# main.net
KiCad netlist of a schematic drawn in Altium Designer
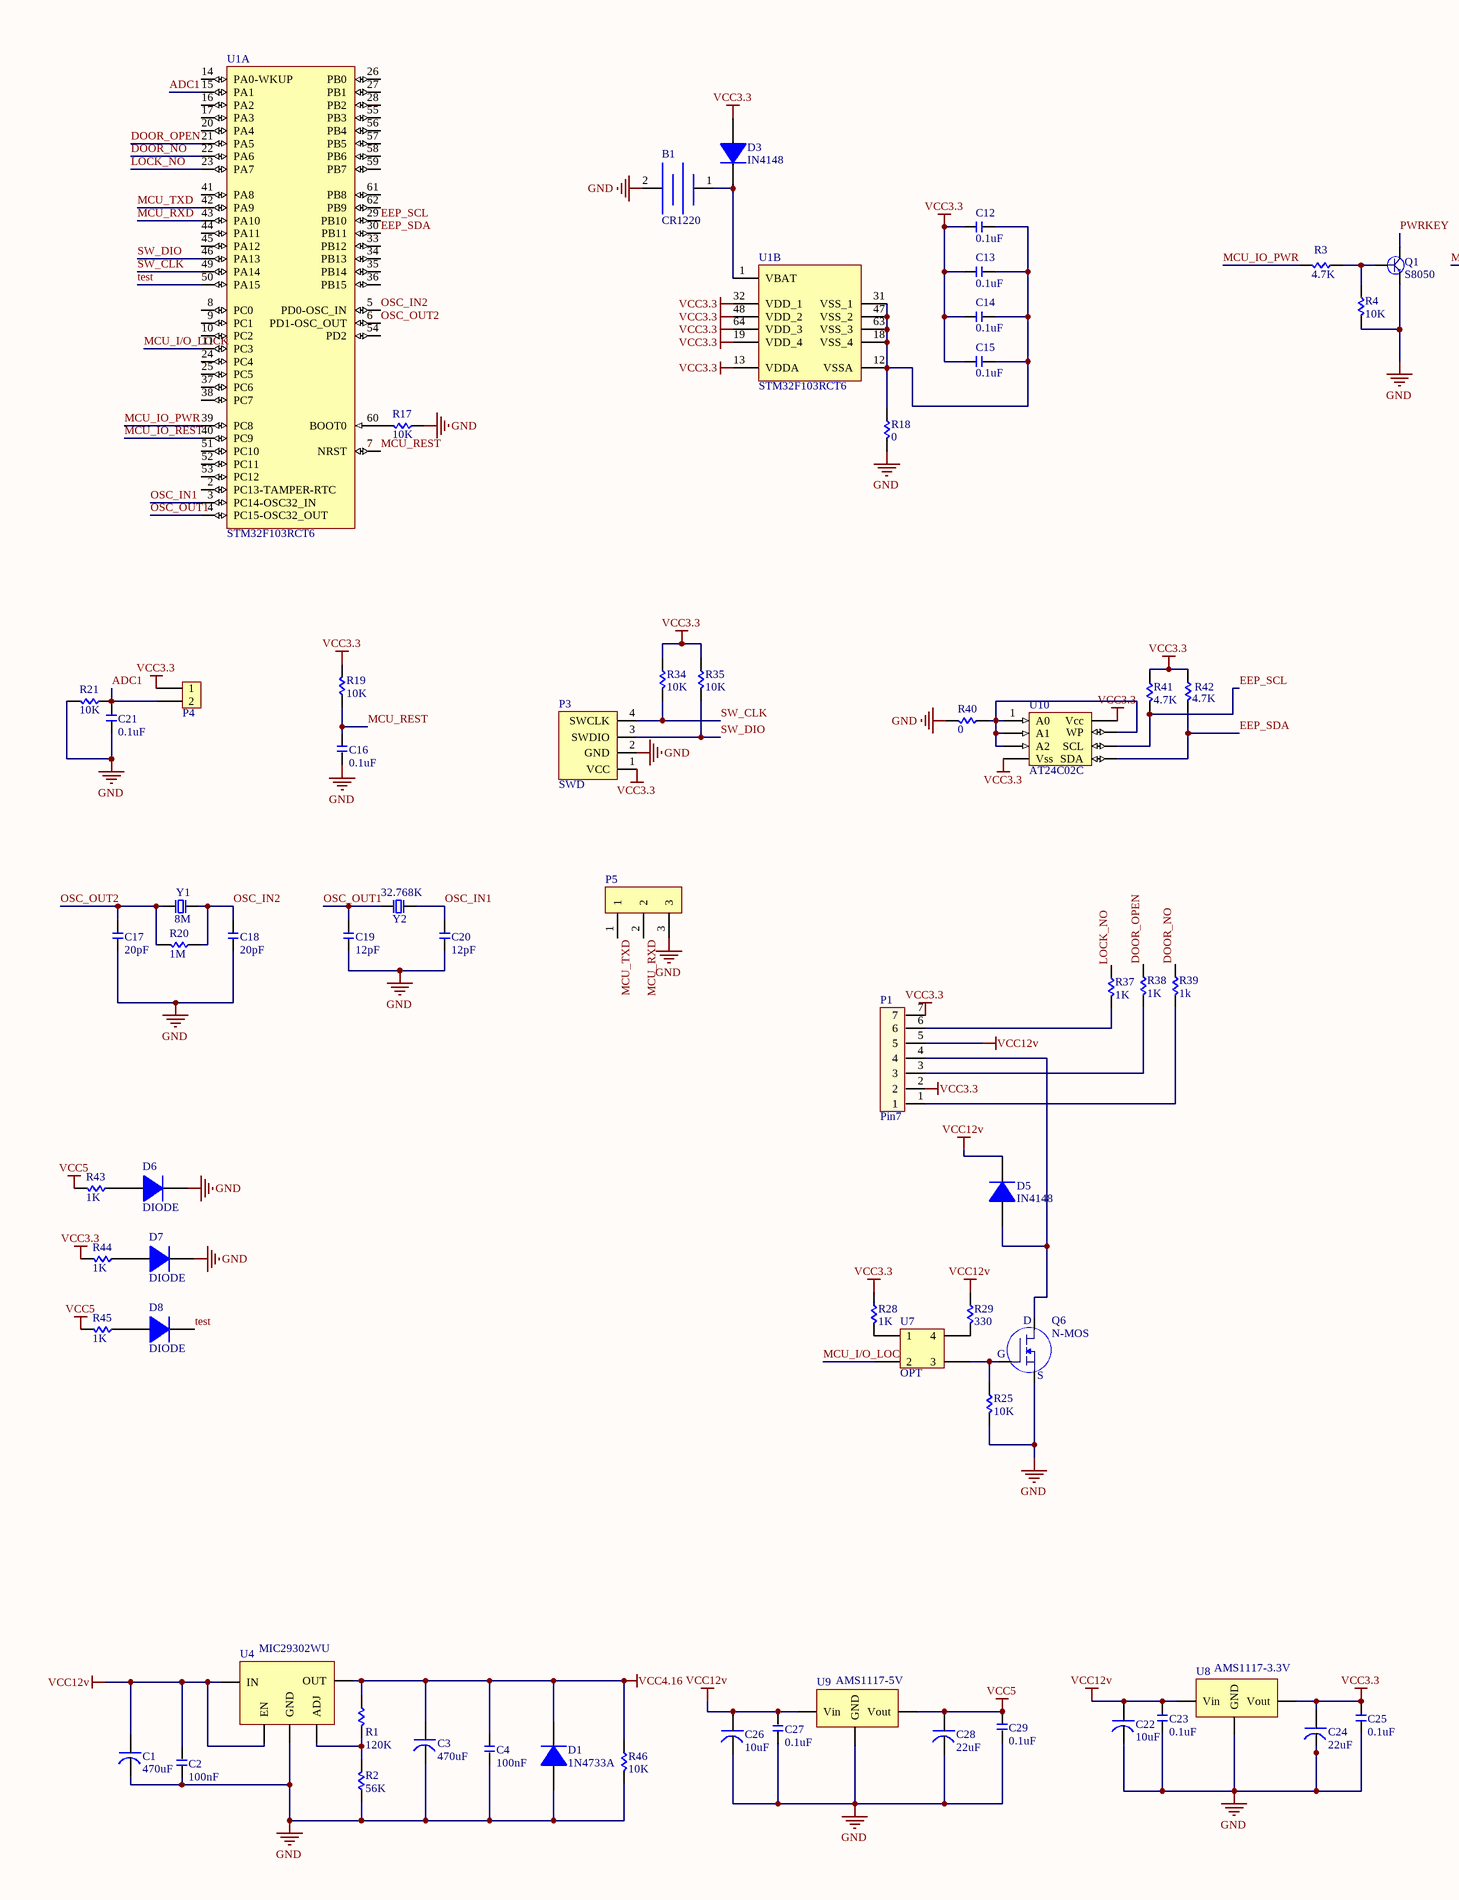
[diagram p0: main.SchDoc, left]
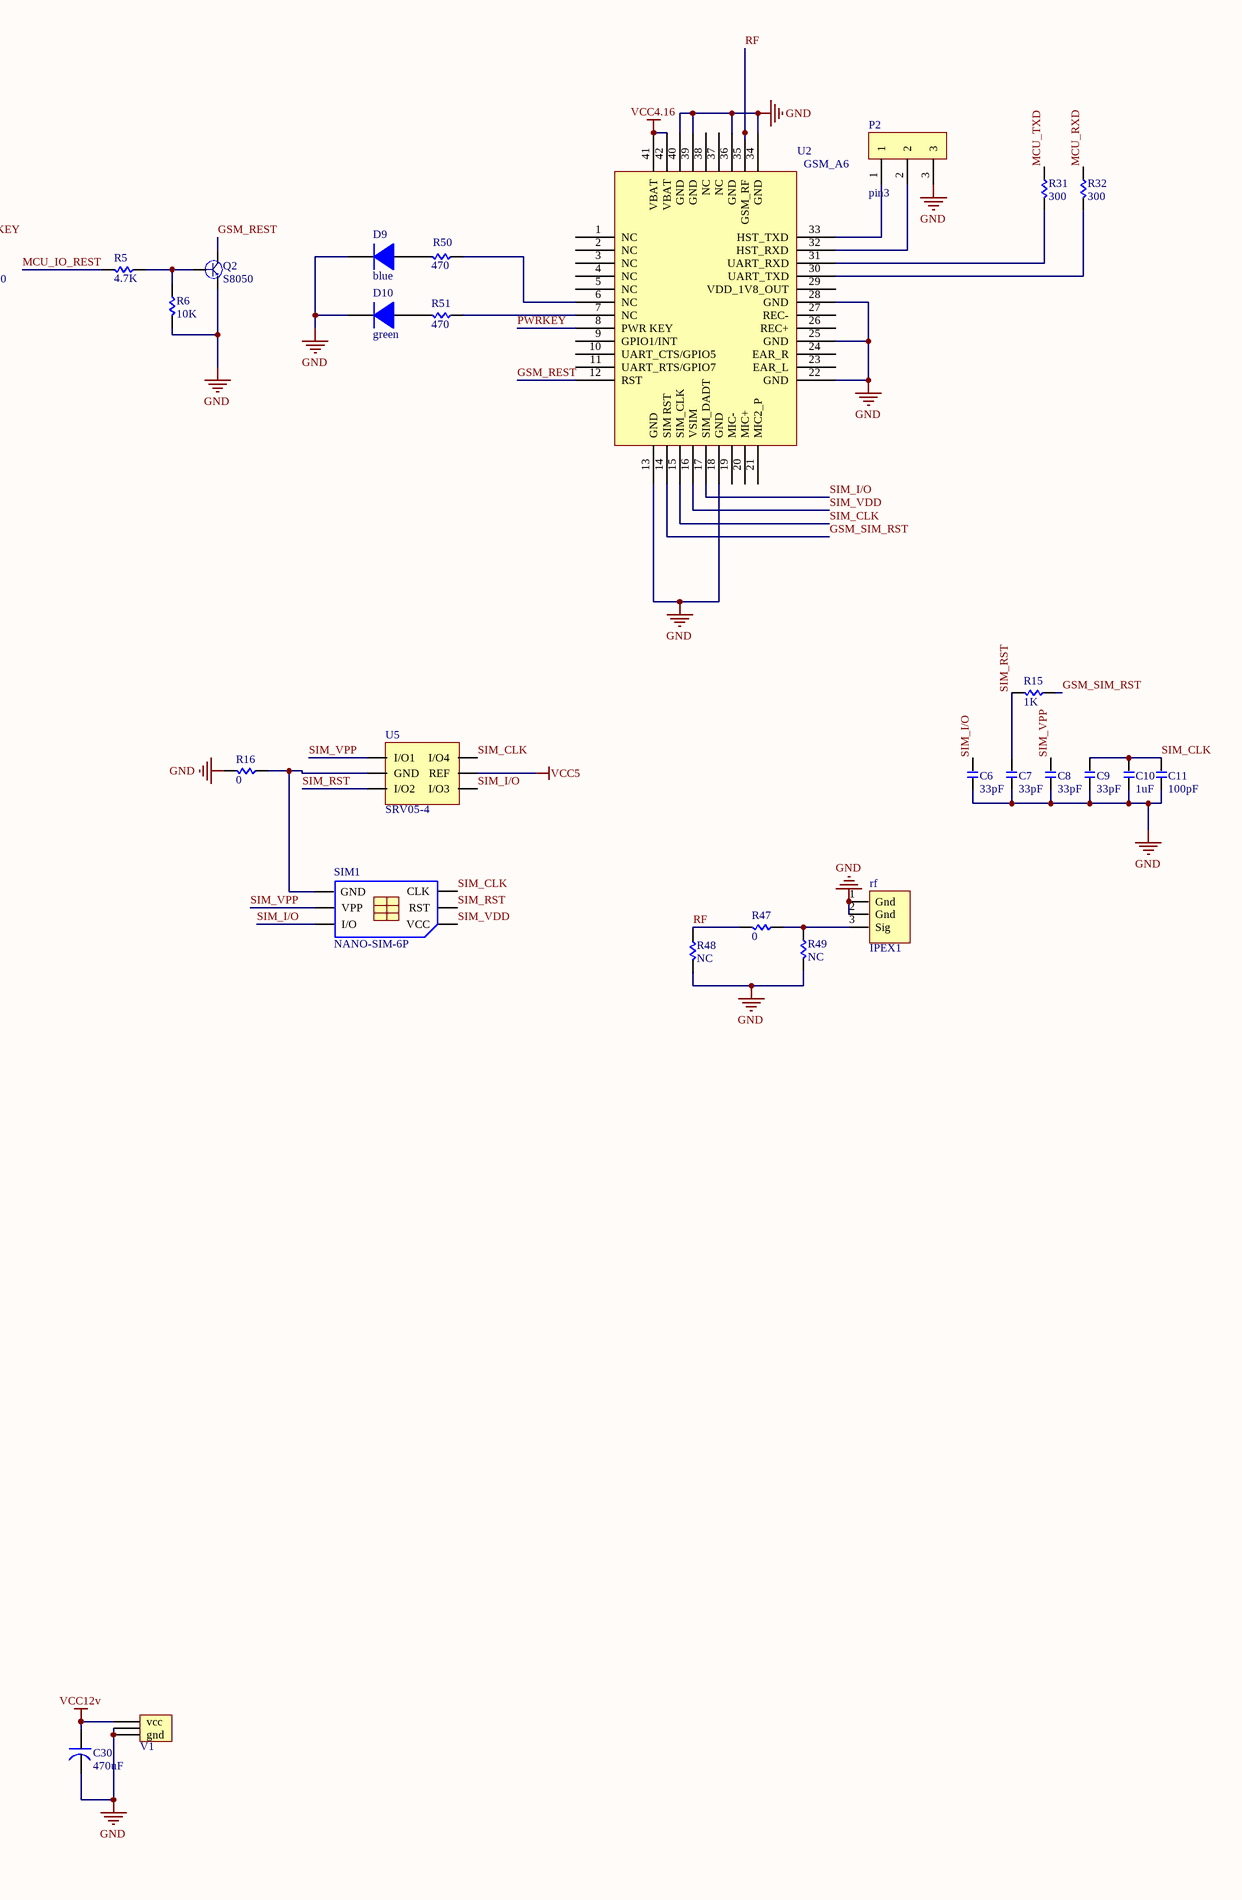
[diagram p1: main.SchDoc, right]

(export (version "E")
  (design (tool "Eeschema 10.0.6"))
  (components
    (comp (ref "B1") (value "CR1220") (footprint "CR1220") (libsource (lib "dev") (part "BAT")))
    (comp (ref "C1") (value "470uF") (footprint "CAP_8.2mm*8.2mm") (libsource (lib "dev") (part "Cap_Elec")))
    (comp (ref "C2") (value "100nF") (footprint "0805") (libsource (lib "dev") (part "Cap")))
    (comp (ref "C3") (value "470uF") (footprint "CAP_8.2mm*8.2mm") (libsource (lib "dev") (part "Cap_Elec")))
    (comp (ref "C4") (value "100nF") (footprint "0805") (libsource (lib "dev") (part "Cap")))
    (comp (ref "C6") (value "33pF") (footprint "0805") (libsource (lib "dev") (part "Cap")))
    (comp (ref "C7") (value "33pF") (footprint "0805") (libsource (lib "dev") (part "Cap")))
    (comp (ref "C8") (value "33pF") (footprint "0805") (libsource (lib "dev") (part "Cap")))
    (comp (ref "C9") (value "33pF") (footprint "0805") (libsource (lib "dev") (part "Cap")))
    (comp (ref "C10") (value "1uF") (footprint "0805") (libsource (lib "dev") (part "Cap")))
    (comp (ref "C11") (value "100pF") (footprint "0805") (libsource (lib "dev") (part "Cap")))
    (comp (ref "C12") (value "0.1uF") (footprint "0805") (libsource (lib "dev") (part "Cap")))
    (comp (ref "C13") (value "0.1uF") (footprint "0805") (libsource (lib "dev") (part "Cap")))
    (comp (ref "C14") (value "0.1uF") (footprint "0805") (libsource (lib "dev") (part "Cap")))
    (comp (ref "C15") (value "0.1uF") (footprint "0805") (libsource (lib "dev") (part "Cap")))
    (comp (ref "C16") (value "0.1uF") (footprint "0805") (libsource (lib "dev") (part "Cap")))
    (comp (ref "C17") (value "20pF") (footprint "0805") (libsource (lib "dev") (part "Cap")))
    (comp (ref "C18") (value "20pF") (footprint "0805") (libsource (lib "dev") (part "Cap")))
    (comp (ref "C19") (value "12pF") (footprint "0805") (libsource (lib "dev") (part "Cap")))
    (comp (ref "C20") (value "12pF") (footprint "0805") (libsource (lib "dev") (part "Cap")))
    (comp (ref "C21") (value "0.1uF") (footprint "0805") (libsource (lib "dev") (part "Cap")))
    (comp (ref "C22") (value "10uF") (footprint "1206") (libsource (lib "dev") (part "Cap_Elec")))
    (comp (ref "C23") (value "0.1uF") (footprint "0805") (libsource (lib "dev") (part "Cap")))
    (comp (ref "C24") (value "22uF") (footprint "1206") (libsource (lib "dev") (part "Cap_Elec")))
    (comp (ref "C25") (value "0.1uF") (footprint "0805") (libsource (lib "dev") (part "Cap")))
    (comp (ref "C26") (value "10uF") (footprint "1206") (libsource (lib "dev") (part "Cap_Elec")))
    (comp (ref "C27") (value "0.1uF") (footprint "0805") (libsource (lib "dev") (part "Cap")))
    (comp (ref "C28") (value "22uF") (footprint "1206") (libsource (lib "dev") (part "Cap_Elec")))
    (comp (ref "C29") (value "0.1uF") (footprint "0805") (libsource (lib "dev") (part "Cap")))
    (comp (ref "C30") (value "470uF") (footprint "DIP2_8.3x3.1") (libsource (lib "dev") (part "Cap_Elec")))
    (comp (ref "D1") (value "1N4733A") (footprint "Dip-6mm") (libsource (lib "dev") (part "DIODE")))
    (comp (ref "D3") (value "IN4148") (footprint "1206") (libsource (lib "dev") (part "DIODE")))
    (comp (ref "D5") (value "IN4148") (footprint "1206") (libsource (lib "dev") (part "DIODE")))
    (comp (ref "D6") (value "DIODE") (footprint "0603") (libsource (lib "dev") (part "DIODE")))
    (comp (ref "D7") (value "DIODE") (footprint "0603") (libsource (lib "dev") (part "DIODE")))
    (comp (ref "D8") (value "DIODE") (footprint "0603") (libsource (lib "dev") (part "DIODE")))
    (comp (ref "D9") (value "blue") (footprint "0603") (libsource (lib "dev") (part "DIODE")))
    (comp (ref "D10") (value "green") (footprint "0603") (libsource (lib "dev") (part "DIODE")))
    (comp (ref "P1") (value "Pin7") (footprint "Pin_7_3.5mm") (libsource (lib "dev") (part "Pin7")))
    (comp (ref "P2") (value "pin3") (footprint "PIN3") (libsource (lib "dev") (part "pin3")))
    (comp (ref "P3") (value "SWD") (footprint "PIN4") (libsource (lib "dev") (part "SWD")))
    (comp (ref "P4") (value "Pin2") (footprint "XH2.54_2") (libsource (lib "dev") (part "Pin2")))
    (comp (ref "P5") (value "pin3") (footprint "PIN3") (libsource (lib "dev") (part "pin3")))
    (comp (ref "Q1") (value "S8050") (footprint "sot-23") (libsource (lib "dev") (part "Npn-Sot-23")))
    (comp (ref "Q2") (value "S8050") (footprint "sot-23") (libsource (lib "dev") (part "Npn-Sot-23")))
    (comp (ref "Q6") (value "N-MOS") (footprint "SOT-23-3") (libsource (lib "dev") (part "N-MOS")))
    (comp (ref "R1") (value "120K") (footprint "0805") (libsource (lib "dev") (part "Res")))
    (comp (ref "R2") (value "56K") (footprint "0805") (libsource (lib "dev") (part "Res")))
    (comp (ref "R3") (value "4.7K") (footprint "0805") (libsource (lib "dev") (part "Res")))
    (comp (ref "R4") (value "10K") (footprint "0805") (libsource (lib "dev") (part "Res")))
    (comp (ref "R5") (value "4.7K") (footprint "0805") (libsource (lib "dev") (part "Res")))
    (comp (ref "R6") (value "10K") (footprint "0805") (libsource (lib "dev") (part "Res")))
    (comp (ref "R15") (value "1K") (footprint "0805") (libsource (lib "dev") (part "Res")))
    (comp (ref "R16") (value "0") (footprint "0603") (libsource (lib "dev") (part "Res")))
    (comp (ref "R17") (value "10K") (footprint "0805") (libsource (lib "dev") (part "Res")))
    (comp (ref "R18") (value "0") (footprint "0603") (libsource (lib "dev") (part "Res")))
    (comp (ref "R19") (value "10K") (footprint "0805") (libsource (lib "dev") (part "Res")))
    (comp (ref "R20") (value "1M") (footprint "0805") (libsource (lib "dev") (part "Res")))
    (comp (ref "R21") (value "10K") (footprint "0805") (libsource (lib "dev") (part "Res")))
    (comp (ref "R25") (value "10K") (footprint "0805") (libsource (lib "dev") (part "Res")))
    (comp (ref "R28") (value "1K") (footprint "0805") (libsource (lib "dev") (part "Res")))
    (comp (ref "R29") (value "330") (footprint "0805") (libsource (lib "dev") (part "Res")))
    (comp (ref "R31") (value "300") (footprint "0805") (libsource (lib "dev") (part "Res")))
    (comp (ref "R32") (value "300") (footprint "0805") (libsource (lib "dev") (part "Res")))
    (comp (ref "R34") (value "10K") (footprint "0805") (libsource (lib "dev") (part "Res")))
    (comp (ref "R35") (value "10K") (footprint "0805") (libsource (lib "dev") (part "Res")))
    (comp (ref "R37") (value "1K") (footprint "0805") (libsource (lib "dev") (part "Res")))
    (comp (ref "R38") (value "1K") (footprint "0805") (libsource (lib "dev") (part "Res")))
    (comp (ref "R39") (value "1k") (footprint "0805") (libsource (lib "dev") (part "Res")))
    (comp (ref "R40") (value "0") (footprint "0603") (libsource (lib "dev") (part "Res")))
    (comp (ref "R41") (value "4.7K") (footprint "0603") (libsource (lib "dev") (part "Res")))
    (comp (ref "R42") (value "4.7K") (footprint "0603") (libsource (lib "dev") (part "Res")))
    (comp (ref "R43") (value "1K") (footprint "0603") (libsource (lib "dev") (part "Res")))
    (comp (ref "R44") (value "1K") (footprint "0603") (libsource (lib "dev") (part "Res")))
    (comp (ref "R45") (value "1K") (footprint "0603") (libsource (lib "dev") (part "Res")))
    (comp (ref "R46") (value "10K") (footprint "0805") (libsource (lib "dev") (part "Res")))
    (comp (ref "R47") (value "0") (footprint "0805") (libsource (lib "dev") (part "Res")))
    (comp (ref "R48") (value "NC") (footprint "0805") (libsource (lib "dev") (part "Res")))
    (comp (ref "R49") (value "NC") (footprint "0805") (libsource (lib "dev") (part "Res")))
    (comp (ref "R50") (value "470") (footprint "0603") (libsource (lib "dev") (part "Res")))
    (comp (ref "R51") (value "470") (footprint "0603") (libsource (lib "dev") (part "Res")))
    (comp (ref "rf") (value "IPEX1") (footprint "IPEX_1") (libsource (lib "dev") (part "IPEX1")))
    (comp (ref "SIM1")
      (value "NANO-SIM-6P")
      (footprint "NANO-SIM-6P")
      (libsource (lib "dev") (part "NANO-SIM-6P"))
    )
    (comp (ref "U1")
      (value "STM32F103RCT6")
      (footprint "STM-LQFP64_M")
      (libsource (lib "STMicroelectronics STM32 F1") (part "STM32F103RCT6"))
    )
    (comp (ref "U2") (value "GSM_A6") (footprint "PCBA6") (libsource (lib "Schlib1") (part "GSM_A6")))
    (comp (ref "U4") (value "MIC29302WU") (footprint "TO-263-5") (libsource (lib "dev") (part "MIC29302WU")))
    (comp (ref "U5") (value "SRV05-4") (footprint "Sot-23-6") (libsource (lib "dev") (part "SRV05-4")))
    (comp (ref "U7") (value "OPT") (footprint "SOP4") (libsource (lib "dev") (part "OPT")))
    (comp (ref "U8")
      (value "AMS1117-3.3V")
      (footprint "SOT-223")
      (libsource (lib "dev") (part "AMS1117-3.3V"))
    )
    (comp (ref "U9") (value "AMS1117-5V") (footprint "SOT-223") (libsource (lib "dev") (part "AMS1117-3.3V")))
    (comp (ref "U10") (value "AT24C02C") (footprint "SOP8") (libsource (lib "dev") (part "AT24C02C")))
    (comp (ref "V1")
      (value "POWER_PIN")
      (footprint "POWER_PIN_PCB")
      (libsource (lib "dev") (part "POWER_PIN"))
    )
    (comp (ref "Y1") (value "8M") (footprint "crystal") (libsource (lib "dev") (part "crystal")))
    (comp (ref "Y2") (value "32.768K") (footprint "PIN1.1") (libsource (lib "dev") (part "crystal")))
  )
  (nets
    (net (code "1") (name "/ADC1") (class "Default")
      (node (ref "C21") (pin "2") (pinfunction "2_2") (pintype "passive"))
      (node (ref "P4") (pin "2") (pinfunction "2_2") (pintype "passive"))
      (node (ref "R21") (pin "2") (pinfunction "2_2") (pintype "passive"))
      (node (ref "U1") (pin "15") (pinfunction "PA1_15") (pintype "bidirectional"))
    )
    (net (code "2") (name "/DOOR_NO") (class "Default")
      (node (ref "R39") (pin "2") (pinfunction "2_2") (pintype "passive"))
      (node (ref "U1") (pin "22") (pinfunction "PA6_22") (pintype "bidirectional"))
    )
    (net (code "3") (name "/DOOR_OPEN") (class "Default")
      (node (ref "R38") (pin "2") (pinfunction "2_2") (pintype "passive"))
      (node (ref "U1") (pin "21") (pinfunction "PA5_21") (pintype "bidirectional"))
    )
    (net (code "4") (name "/EEP_SCL") (class "Default")
      (node (ref "R41") (pin "1") (pinfunction "1_1") (pintype "passive"))
      (node (ref "U1") (pin "29") (pinfunction "PB10_29") (pintype "bidirectional"))
      (node (ref "U10") (pin "6") (pinfunction "SCL_6") (pintype "bidirectional"))
    )
    (net (code "5") (name "/EEP_SDA") (class "Default")
      (node (ref "R42") (pin "1") (pinfunction "1_1") (pintype "passive"))
      (node (ref "U1") (pin "30") (pinfunction "PB11_30") (pintype "bidirectional"))
      (node (ref "U10") (pin "5") (pinfunction "SDA_5") (pintype "bidirectional"))
    )
    (net (code "6") (name "/GSM_REST") (class "Default")
      (node (ref "Q2") (pin "3") (pinfunction "3_3") (pintype "passive"))
      (node (ref "U2") (pin "12") (pinfunction "RST_12") (pintype "passive"))
    )
    (net (code "7") (name "/GSM_SIM_RST") (class "Default")
      (node (ref "R15") (pin "2") (pinfunction "2_2") (pintype "passive"))
      (node (ref "U2") (pin "14") (pinfunction "SIM_RST_14") (pintype "passive"))
    )
    (net (code "8") (name "/LOCK_NO") (class "Default")
      (node (ref "R37") (pin "2") (pinfunction "2_2") (pintype "passive"))
      (node (ref "U1") (pin "23") (pinfunction "PA7_23") (pintype "bidirectional"))
    )
    (net (code "9") (name "/MCU_IO_PWR") (class "Default")
      (node (ref "R3") (pin "1") (pinfunction "1_1") (pintype "passive"))
      (node (ref "U1") (pin "39") (pinfunction "PC8_39") (pintype "bidirectional"))
    )
    (net (code "10") (name "/MCU_IO_REST") (class "Default")
      (node (ref "R5") (pin "1") (pinfunction "1_1") (pintype "passive"))
      (node (ref "U1") (pin "40") (pinfunction "PC9_40") (pintype "bidirectional"))
    )
    (net (code "11") (name "/MCU_I{slash}O_LOCK") (class "Default")
      (node (ref "U1") (pin "11") (pinfunction "PC3_11") (pintype "bidirectional"))
      (node (ref "U7") (pin "2") (pinfunction "2_2") (pintype "passive"))
    )
    (net (code "12") (name "/MCU_REST") (class "Default")
      (node (ref "C16") (pin "1") (pinfunction "1_1") (pintype "passive"))
      (node (ref "R19") (pin "2") (pinfunction "2_2") (pintype "passive"))
      (node (ref "U1") (pin "7") (pinfunction "NRST_7") (pintype "bidirectional"))
    )
    (net (code "13") (name "/MCU_RXD") (class "Default")
      (node (ref "P5") (pin "2") (pinfunction "2_2") (pintype "passive"))
      (node (ref "R32") (pin "2") (pinfunction "2_2") (pintype "passive"))
      (node (ref "U1") (pin "43") (pinfunction "PA10_43") (pintype "bidirectional"))
    )
    (net (code "14") (name "/MCU_TXD") (class "Default")
      (node (ref "P5") (pin "1") (pinfunction "1_1") (pintype "passive"))
      (node (ref "R31") (pin "2") (pinfunction "2_2") (pintype "passive"))
      (node (ref "U1") (pin "42") (pinfunction "PA9_42") (pintype "bidirectional"))
    )
    (net (code "15") (name "/OSC_IN1") (class "Default")
      (node (ref "C20") (pin "2") (pinfunction "2_2") (pintype "passive"))
      (node (ref "U1") (pin "3") (pinfunction "PC14-OSC32_IN_3") (pintype "bidirectional"))
      (node (ref "Y2") (pin "2") (pinfunction "2_2") (pintype "passive"))
    )
    (net (code "16") (name "/OSC_IN2") (class "Default")
      (node (ref "C18") (pin "2") (pinfunction "2_2") (pintype "passive"))
      (node (ref "R20") (pin "2") (pinfunction "2_2") (pintype "passive"))
      (node (ref "U1") (pin "5") (pinfunction "PD0-OSC_IN_5") (pintype "bidirectional"))
      (node (ref "Y1") (pin "2") (pinfunction "2_2") (pintype "passive"))
    )
    (net (code "17") (name "/OSC_OUT1") (class "Default")
      (node (ref "C19") (pin "2") (pinfunction "2_2") (pintype "passive"))
      (node (ref "U1") (pin "4") (pinfunction "PC15-OSC32_OUT_4") (pintype "bidirectional"))
      (node (ref "Y2") (pin "1") (pinfunction "1_1") (pintype "passive"))
    )
    (net (code "18") (name "/OSC_OUT2") (class "Default")
      (node (ref "C17") (pin "2") (pinfunction "2_2") (pintype "passive"))
      (node (ref "R20") (pin "1") (pinfunction "1_1") (pintype "passive"))
      (node (ref "U1") (pin "6") (pinfunction "PD1-OSC_OUT_6") (pintype "bidirectional"))
      (node (ref "Y1") (pin "1") (pinfunction "1_1") (pintype "passive"))
    )
    (net (code "19") (name "/PWRKEY") (class "Default")
      (node (ref "Q1") (pin "3") (pinfunction "3_3") (pintype "passive"))
      (node (ref "U2") (pin "8") (pinfunction "PWR_KEY_8") (pintype "passive"))
    )
    (net (code "20") (name "/RF") (class "Default")
      (node (ref "R47") (pin "1") (pinfunction "1_1") (pintype "passive"))
      (node (ref "R48") (pin "2") (pinfunction "2_2") (pintype "passive"))
      (node (ref "U2") (pin "35") (pinfunction "GSM_RF_35") (pintype "passive"))
    )
    (net (code "21") (name "/SIM_CLK") (class "Default")
      (node (ref "C10") (pin "2") (pinfunction "2_2") (pintype "passive"))
      (node (ref "C11") (pin "2") (pinfunction "2_2") (pintype "passive"))
      (node (ref "C9") (pin "2") (pinfunction "2_2") (pintype "passive"))
      (node (ref "SIM1") (pin "3") (pinfunction "CLK_3") (pintype "passive"))
      (node (ref "U2") (pin "15") (pinfunction "SIM_CLK_15") (pintype "passive"))
      (node (ref "U5") (pin "6") (pinfunction "I/O4_6") (pintype "passive"))
    )
    (net (code "22") (name "/SIM_I{slash}O") (class "Default")
      (node (ref "C6") (pin "2") (pinfunction "2_2") (pintype "passive"))
      (node (ref "SIM1") (pin "7") (pinfunction "I/O_7") (pintype "passive"))
      (node (ref "U2") (pin "17") (pinfunction "SIM_DADT_17") (pintype "passive"))
      (node (ref "U5") (pin "4") (pinfunction "I/O3_4") (pintype "passive"))
    )
    (net (code "23") (name "/SIM_RST") (class "Default")
      (node (ref "C7") (pin "2") (pinfunction "2_2") (pintype "passive"))
      (node (ref "R15") (pin "1") (pinfunction "1_1") (pintype "passive"))
      (node (ref "SIM1") (pin "2") (pinfunction "RST_2") (pintype "passive"))
      (node (ref "U5") (pin "3") (pinfunction "I/O2_3") (pintype "passive"))
    )
    (net (code "24") (name "/SIM_VDD") (class "Default")
      (node (ref "SIM1") (pin "1") (pinfunction "VCC_1") (pintype "passive"))
      (node (ref "U2") (pin "16") (pinfunction "VSIM_16") (pintype "passive"))
    )
    (net (code "25") (name "/SIM_VPP") (class "Default")
      (node (ref "C8") (pin "2") (pinfunction "2_2") (pintype "passive"))
      (node (ref "SIM1") (pin "6") (pinfunction "VPP_6") (pintype "passive"))
      (node (ref "U5") (pin "1") (pinfunction "I/O1_1") (pintype "passive"))
    )
    (net (code "26") (name "/SW_CLK") (class "Default")
      (node (ref "P3") (pin "4") (pinfunction "SWCLK_4") (pintype "passive"))
      (node (ref "R34") (pin "1") (pinfunction "1_1") (pintype "passive"))
      (node (ref "U1") (pin "49") (pinfunction "PA14_49") (pintype "bidirectional"))
    )
    (net (code "27") (name "/SW_DIO") (class "Default")
      (node (ref "P3") (pin "3") (pinfunction "SWDIO_3") (pintype "passive"))
      (node (ref "R35") (pin "1") (pinfunction "1_1") (pintype "passive"))
      (node (ref "U1") (pin "46") (pinfunction "PA13_46") (pintype "bidirectional"))
    )
    (net (code "28") (name "/test") (class "Default")
      (node (ref "D8") (pin "2") (pinfunction "2_2") (pintype "passive"))
      (node (ref "U1") (pin "50") (pinfunction "PA15_50") (pintype "bidirectional"))
    )
    (net (code "29") (name "GND") (class "Default")
      (node (ref "B1") (pin "2") (pinfunction "2_2") (pintype "passive"))
      (node (ref "C1") (pin "2") (pinfunction "2_2") (pintype "passive"))
      (node (ref "C10") (pin "1") (pinfunction "1_1") (pintype "passive"))
      (node (ref "C11") (pin "1") (pinfunction "1_1") (pintype "passive"))
      (node (ref "C16") (pin "2") (pinfunction "2_2") (pintype "passive"))
      (node (ref "C17") (pin "1") (pinfunction "1_1") (pintype "passive"))
      (node (ref "C18") (pin "1") (pinfunction "1_1") (pintype "passive"))
      (node (ref "C19") (pin "1") (pinfunction "1_1") (pintype "passive"))
      (node (ref "C2") (pin "1") (pinfunction "1_1") (pintype "passive"))
      (node (ref "C20") (pin "1") (pinfunction "1_1") (pintype "passive"))
      (node (ref "C21") (pin "1") (pinfunction "1_1") (pintype "passive"))
      (node (ref "C22") (pin "2") (pinfunction "2_2") (pintype "passive"))
      (node (ref "C23") (pin "1") (pinfunction "1_1") (pintype "passive"))
      (node (ref "C24") (pin "2") (pinfunction "2_2") (pintype "passive"))
      (node (ref "C25") (pin "1") (pinfunction "1_1") (pintype "passive"))
      (node (ref "C26") (pin "2") (pinfunction "2_2") (pintype "passive"))
      (node (ref "C27") (pin "1") (pinfunction "1_1") (pintype "passive"))
      (node (ref "C28") (pin "2") (pinfunction "2_2") (pintype "passive"))
      (node (ref "C29") (pin "2") (pinfunction "2_2") (pintype "passive"))
      (node (ref "C3") (pin "2") (pinfunction "2_2") (pintype "passive"))
      (node (ref "C30") (pin "2") (pinfunction "2_2") (pintype "passive"))
      (node (ref "C4") (pin "2") (pinfunction "2_2") (pintype "passive"))
      (node (ref "C6") (pin "1") (pinfunction "1_1") (pintype "passive"))
      (node (ref "C7") (pin "1") (pinfunction "1_1") (pintype "passive"))
      (node (ref "C8") (pin "1") (pinfunction "1_1") (pintype "passive"))
      (node (ref "C9") (pin "1") (pinfunction "1_1") (pintype "passive"))
      (node (ref "D1") (pin "1") (pinfunction "1_1") (pintype "passive"))
      (node (ref "D10") (pin "2") (pinfunction "2_2") (pintype "passive"))
      (node (ref "D6") (pin "2") (pinfunction "2_2") (pintype "passive"))
      (node (ref "D7") (pin "2") (pinfunction "2_2") (pintype "passive"))
      (node (ref "D9") (pin "2") (pinfunction "2_2") (pintype "passive"))
      (node (ref "P2") (pin "3") (pinfunction "3_3") (pintype "passive"))
      (node (ref "P3") (pin "2") (pinfunction "GND_2") (pintype "passive"))
      (node (ref "P5") (pin "3") (pinfunction "3_3") (pintype "passive"))
      (node (ref "Q1") (pin "2") (pinfunction "2_2") (pintype "passive"))
      (node (ref "Q2") (pin "2") (pinfunction "2_2") (pintype "passive"))
      (node (ref "Q6") (pin "2") (pinfunction "S_2") (pintype "passive"))
      (node (ref "R16") (pin "1") (pinfunction "1_1") (pintype "passive"))
      (node (ref "R17") (pin "2") (pinfunction "2_2") (pintype "passive"))
      (node (ref "R18") (pin "1") (pinfunction "1_1") (pintype "passive"))
      (node (ref "R2") (pin "2") (pinfunction "2_2") (pintype "passive"))
      (node (ref "R21") (pin "1") (pinfunction "1_1") (pintype "passive"))
      (node (ref "R25") (pin "1") (pinfunction "1_1") (pintype "passive"))
      (node (ref "R4") (pin "1") (pinfunction "1_1") (pintype "passive"))
      (node (ref "R40") (pin "1") (pinfunction "1_1") (pintype "passive"))
      (node (ref "R46") (pin "1") (pinfunction "1_1") (pintype "passive"))
      (node (ref "R48") (pin "1") (pinfunction "1_1") (pintype "passive"))
      (node (ref "R49") (pin "1") (pinfunction "1_1") (pintype "passive"))
      (node (ref "R6") (pin "1") (pinfunction "1_1") (pintype "passive"))
      (node (ref "U2") (pin "13") (pinfunction "GND_13") (pintype "passive"))
      (node (ref "U2") (pin "18") (pinfunction "GND_18") (pintype "passive"))
      (node (ref "U2") (pin "22") (pinfunction "GND_22") (pintype "passive"))
      (node (ref "U2") (pin "25") (pinfunction "GND_25") (pintype "passive"))
      (node (ref "U2") (pin "28") (pinfunction "GND_28") (pintype "passive"))
      (node (ref "U2") (pin "34") (pinfunction "GND_34") (pintype "passive"))
      (node (ref "U2") (pin "36") (pinfunction "GND_36") (pintype "passive"))
      (node (ref "U2") (pin "39") (pinfunction "GND_39") (pintype "passive"))
      (node (ref "U2") (pin "40") (pinfunction "GND_40") (pintype "passive"))
      (node (ref "U4") (pin "3") (pinfunction "GND_3") (pintype "passive"))
      (node (ref "U8") (pin "1") (pinfunction "GND_1") (pintype "power_in"))
      (node (ref "U9") (pin "1") (pinfunction "GND_1") (pintype "power_in"))
      (node (ref "V1") (pin "2") (pinfunction "gnd_2") (pintype "passive"))
      (node (ref "V1") (pin "3") (pinfunction "3_3") (pintype "passive"))
      (node (ref "rf") (pin "1") (pinfunction "Gnd_1") (pintype "passive"))
      (node (ref "rf") (pin "2") (pinfunction "Gnd_2") (pintype "passive"))
    )
    (net (code "30") (name "Net-(B1-VCC)") (class "Default")
      (node (ref "B1") (pin "1") (pinfunction "VCC_1") (pintype "passive"))
      (node (ref "D3") (pin "2") (pinfunction "2_2") (pintype "passive"))
      (node (ref "U1") (pin "1") (pinfunction "VBAT_1") (pintype "power_in"))
    )
    (net (code "31") (name "Net-(D6-Pad1)") (class "Default")
      (node (ref "D6") (pin "1") (pinfunction "1_1") (pintype "passive"))
      (node (ref "R43") (pin "2") (pinfunction "2_2") (pintype "passive"))
    )
    (net (code "32") (name "Net-(D7-Pad1)") (class "Default")
      (node (ref "D7") (pin "1") (pinfunction "1_1") (pintype "passive"))
      (node (ref "R44") (pin "2") (pinfunction "2_2") (pintype "passive"))
    )
    (net (code "33") (name "Net-(D8-Pad1)") (class "Default")
      (node (ref "D8") (pin "1") (pinfunction "1_1") (pintype "passive"))
      (node (ref "R45") (pin "2") (pinfunction "2_2") (pintype "passive"))
    )
    (net (code "34") (name "Net-(D9-Pad1)") (class "Default")
      (node (ref "D9") (pin "1") (pinfunction "1_1") (pintype "passive"))
      (node (ref "R50") (pin "1") (pinfunction "1_1") (pintype "passive"))
    )
    (net (code "35") (name "Net-(D10-Pad1)") (class "Default")
      (node (ref "D10") (pin "1") (pinfunction "1_1") (pintype "passive"))
      (node (ref "R51") (pin "1") (pinfunction "1_1") (pintype "passive"))
    )
    (net (code "36") (name "Net-(P1-Pad1)") (class "Default")
      (node (ref "P1") (pin "1") (pinfunction "1_1") (pintype "passive"))
      (node (ref "R39") (pin "1") (pinfunction "1_1") (pintype "passive"))
    )
    (net (code "37") (name "Net-(P1-Pad3)") (class "Default")
      (node (ref "P1") (pin "3") (pinfunction "3_3") (pintype "passive"))
      (node (ref "R38") (pin "1") (pinfunction "1_1") (pintype "passive"))
    )
    (net (code "38") (name "Net-(P1-Pad6)") (class "Default")
      (node (ref "P1") (pin "6") (pinfunction "6_6") (pintype "passive"))
      (node (ref "R37") (pin "1") (pinfunction "1_1") (pintype "passive"))
    )
    (net (code "39") (name "Net-(Q1-Pad1)") (class "Default")
      (node (ref "Q1") (pin "1") (pinfunction "1_1") (pintype "passive"))
      (node (ref "R3") (pin "2") (pinfunction "2_2") (pintype "passive"))
      (node (ref "R4") (pin "2") (pinfunction "2_2") (pintype "passive"))
    )
    (net (code "40") (name "Net-(Q2-Pad1)") (class "Default")
      (node (ref "Q2") (pin "1") (pinfunction "1_1") (pintype "passive"))
      (node (ref "R5") (pin "2") (pinfunction "2_2") (pintype "passive"))
      (node (ref "R6") (pin "2") (pinfunction "2_2") (pintype "passive"))
    )
    (net (code "41") (name "Net-(Q6-D)") (class "Default")
      (node (ref "D5") (pin "1") (pinfunction "1_1") (pintype "passive"))
      (node (ref "P1") (pin "4") (pinfunction "4_4") (pintype "passive"))
      (node (ref "Q6") (pin "3") (pinfunction "D_3") (pintype "passive"))
    )
    (net (code "42") (name "Net-(Q6-G)") (class "Default")
      (node (ref "Q6") (pin "1") (pinfunction "G_1") (pintype "passive"))
      (node (ref "R25") (pin "2") (pinfunction "2_2") (pintype "passive"))
      (node (ref "U7") (pin "3") (pinfunction "3_3") (pintype "passive"))
    )
    (net (code "43") (name "Net-(R28-Pad1)") (class "Default")
      (node (ref "R28") (pin "1") (pinfunction "1_1") (pintype "passive"))
      (node (ref "U7") (pin "1") (pinfunction "1_1") (pintype "passive"))
    )
    (net (code "44") (name "Net-(R29-Pad1)") (class "Default")
      (node (ref "R29") (pin "1") (pinfunction "1_1") (pintype "passive"))
      (node (ref "U7") (pin "4") (pinfunction "4_4") (pintype "passive"))
    )
    (net (code "45") (name "Net-(R50-Pad2)") (class "Default")
      (node (ref "R50") (pin "2") (pinfunction "2_2") (pintype "passive"))
      (node (ref "U2") (pin "6") (pinfunction "NC_6") (pintype "passive"))
    )
    (net (code "46") (name "Net-(R51-Pad2)") (class "Default")
      (node (ref "R51") (pin "2") (pinfunction "2_2") (pintype "passive"))
      (node (ref "U2") (pin "7") (pinfunction "NC_7") (pintype "passive"))
    )
    (net (code "47") (name "Net-(SIM1-GND)") (class "Default")
      (node (ref "R16") (pin "2") (pinfunction "2_2") (pintype "passive"))
      (node (ref "SIM1") (pin "5") (pinfunction "GND_5") (pintype "passive"))
      (node (ref "U5") (pin "2") (pinfunction "GND_2") (pintype "passive"))
    )
    (net (code "48") (name "Net-(U1A-BOOT0)") (class "Default")
      (node (ref "R17") (pin "1") (pinfunction "1_1") (pintype "passive"))
      (node (ref "U1") (pin "60") (pinfunction "BOOT0_60") (pintype "input"))
    )
    (net (code "49") (name "Net-(U1B-VSSA)") (class "Default")
      (node (ref "C12") (pin "2") (pinfunction "2_2") (pintype "passive"))
      (node (ref "C13") (pin "2") (pinfunction "2_2") (pintype "passive"))
      (node (ref "C14") (pin "2") (pinfunction "2_2") (pintype "passive"))
      (node (ref "C15") (pin "2") (pinfunction "2_2") (pintype "passive"))
      (node (ref "R18") (pin "2") (pinfunction "2_2") (pintype "passive"))
      (node (ref "U1") (pin "12") (pinfunction "VSSA_12") (pintype "power_in"))
      (node (ref "U1") (pin "18") (pinfunction "VSS_4_18") (pintype "power_in"))
      (node (ref "U1") (pin "31") (pinfunction "VSS_1_31") (pintype "power_in"))
      (node (ref "U1") (pin "47") (pinfunction "VSS_2_47") (pintype "power_in"))
      (node (ref "U1") (pin "63") (pinfunction "VSS_3_63") (pintype "power_in"))
    )
    (net (code "50") (name "Net-(U2-HST_RXD)") (class "Default")
      (node (ref "P2") (pin "2") (pinfunction "2_2") (pintype "passive"))
      (node (ref "U2") (pin "32") (pinfunction "HST_RXD_32") (pintype "passive"))
    )
    (net (code "51") (name "Net-(U2-HST_TXD)") (class "Default")
      (node (ref "P2") (pin "1") (pinfunction "1_1") (pintype "passive"))
      (node (ref "U2") (pin "33") (pinfunction "HST_TXD_33") (pintype "passive"))
    )
    (net (code "52") (name "Net-(U2-UART_RXD)") (class "Default")
      (node (ref "R31") (pin "1") (pinfunction "1_1") (pintype "passive"))
      (node (ref "U2") (pin "31") (pinfunction "UART_RXD_31") (pintype "passive"))
    )
    (net (code "53") (name "Net-(U2-UART_TXD)") (class "Default")
      (node (ref "R32") (pin "1") (pinfunction "1_1") (pintype "passive"))
      (node (ref "U2") (pin "30") (pinfunction "UART_TXD_30") (pintype "passive"))
    )
    (net (code "54") (name "Net-(U4-ADJ)") (class "Default")
      (node (ref "R1") (pin "1") (pinfunction "1_1") (pintype "passive"))
      (node (ref "R2") (pin "1") (pinfunction "1_1") (pintype "passive"))
      (node (ref "U4") (pin "5") (pinfunction "ADJ_5") (pintype "passive"))
    )
    (net (code "55") (name "Net-(U10-A0)") (class "Default")
      (node (ref "R40") (pin "2") (pinfunction "2_2") (pintype "passive"))
      (node (ref "U10") (pin "1") (pinfunction "A0_1") (pintype "input"))
      (node (ref "U10") (pin "2") (pinfunction "A1_2") (pintype "input"))
      (node (ref "U10") (pin "3") (pinfunction "A2_3") (pintype "input"))
      (node (ref "U10") (pin "7") (pinfunction "WP_7") (pintype "bidirectional"))
    )
    (net (code "56") (name "Net-(rf-Sig)") (class "Default")
      (node (ref "R47") (pin "2") (pinfunction "2_2") (pintype "passive"))
      (node (ref "R49") (pin "2") (pinfunction "2_2") (pintype "passive"))
      (node (ref "rf") (pin "3") (pinfunction "Sig_3") (pintype "passive"))
    )
    (net (code "57") (name "VCC3.3") (class "Default")
      (node (ref "C12") (pin "1") (pinfunction "1_1") (pintype "passive"))
      (node (ref "C13") (pin "1") (pinfunction "1_1") (pintype "passive"))
      (node (ref "C14") (pin "1") (pinfunction "1_1") (pintype "passive"))
      (node (ref "C15") (pin "1") (pinfunction "1_1") (pintype "passive"))
      (node (ref "C24") (pin "1") (pinfunction "1_1") (pintype "passive"))
      (node (ref "C25") (pin "2") (pinfunction "2_2") (pintype "passive"))
      (node (ref "D3") (pin "1") (pinfunction "1_1") (pintype "passive"))
      (node (ref "P1") (pin "2") (pinfunction "2_2") (pintype "passive"))
      (node (ref "P1") (pin "7") (pinfunction "7_7") (pintype "passive"))
      (node (ref "P3") (pin "1") (pinfunction "VCC_1") (pintype "passive"))
      (node (ref "P4") (pin "1") (pinfunction "1_1") (pintype "passive"))
      (node (ref "R19") (pin "1") (pinfunction "1_1") (pintype "passive"))
      (node (ref "R28") (pin "2") (pinfunction "2_2") (pintype "passive"))
      (node (ref "R34") (pin "2") (pinfunction "2_2") (pintype "passive"))
      (node (ref "R35") (pin "2") (pinfunction "2_2") (pintype "passive"))
      (node (ref "R41") (pin "2") (pinfunction "2_2") (pintype "passive"))
      (node (ref "R42") (pin "2") (pinfunction "2_2") (pintype "passive"))
      (node (ref "R44") (pin "1") (pinfunction "1_1") (pintype "passive"))
      (node (ref "U1") (pin "13") (pinfunction "VDDA_13") (pintype "power_in"))
      (node (ref "U1") (pin "19") (pinfunction "VDD_4_19") (pintype "power_in"))
      (node (ref "U1") (pin "32") (pinfunction "VDD_1_32") (pintype "power_in"))
      (node (ref "U1") (pin "48") (pinfunction "VDD_2_48") (pintype "power_in"))
      (node (ref "U1") (pin "64") (pinfunction "VDD_3_64") (pintype "power_in"))
      (node (ref "U10") (pin "4") (pinfunction "Vss_4") (pintype "power_in"))
      (node (ref "U10") (pin "8") (pinfunction "Vcc_8") (pintype "power_in"))
      (node (ref "U8") (pin "2") (pinfunction "Vout_2") (pintype "passive"))
    )
    (net (code "58") (name "VCC4.16") (class "Default")
      (node (ref "C3") (pin "1") (pinfunction "1_1") (pintype "passive"))
      (node (ref "C4") (pin "1") (pinfunction "1_1") (pintype "passive"))
      (node (ref "D1") (pin "2") (pinfunction "2_2") (pintype "passive"))
      (node (ref "R1") (pin "2") (pinfunction "2_2") (pintype "passive"))
      (node (ref "R46") (pin "2") (pinfunction "2_2") (pintype "passive"))
      (node (ref "U2") (pin "41") (pinfunction "VBAT_41") (pintype "passive"))
      (node (ref "U2") (pin "42") (pinfunction "VBAT_42") (pintype "passive"))
      (node (ref "U4") (pin "4") (pinfunction "OUT_4") (pintype "passive"))
    )
    (net (code "59") (name "VCC5") (class "Default")
      (node (ref "C28") (pin "1") (pinfunction "1_1") (pintype "passive"))
      (node (ref "C29") (pin "1") (pinfunction "1_1") (pintype "passive"))
      (node (ref "R43") (pin "1") (pinfunction "1_1") (pintype "passive"))
      (node (ref "R45") (pin "1") (pinfunction "1_1") (pintype "passive"))
      (node (ref "U5") (pin "5") (pinfunction "REF_5") (pintype "passive"))
      (node (ref "U9") (pin "2") (pinfunction "Vout_2") (pintype "passive"))
    )
    (net (code "60") (name "VCC12v") (class "Default")
      (node (ref "C1") (pin "1") (pinfunction "1_1") (pintype "passive"))
      (node (ref "C2") (pin "2") (pinfunction "2_2") (pintype "passive"))
      (node (ref "C22") (pin "1") (pinfunction "1_1") (pintype "passive"))
      (node (ref "C23") (pin "2") (pinfunction "2_2") (pintype "passive"))
      (node (ref "C26") (pin "1") (pinfunction "1_1") (pintype "passive"))
      (node (ref "C27") (pin "2") (pinfunction "2_2") (pintype "passive"))
      (node (ref "C30") (pin "1") (pinfunction "1_1") (pintype "passive"))
      (node (ref "D5") (pin "2") (pinfunction "2_2") (pintype "passive"))
      (node (ref "P1") (pin "5") (pinfunction "5_5") (pintype "passive"))
      (node (ref "R29") (pin "2") (pinfunction "2_2") (pintype "passive"))
      (node (ref "U4") (pin "1") (pinfunction "EN_1") (pintype "passive"))
      (node (ref "U4") (pin "2") (pinfunction "IN_2") (pintype "passive"))
      (node (ref "U8") (pin "3") (pinfunction "Vin_3") (pintype "power_in"))
      (node (ref "U9") (pin "3") (pinfunction "Vin_3") (pintype "power_in"))
      (node (ref "V1") (pin "1") (pinfunction "vcc_1") (pintype "passive"))
    )
    (net (code "61") (name "unconnected-(U1A-PA0-WKUP-Pad14)") (class "Default")
      (node (ref "U1") (pin "14") (pinfunction "PA0-WKUP_14") (pintype "bidirectional"))
    )
    (net (code "62") (name "unconnected-(U1A-PA2-Pad16)") (class "Default")
      (node (ref "U1") (pin "16") (pinfunction "PA2_16") (pintype "bidirectional"))
    )
    (net (code "63") (name "unconnected-(U1A-PA3-Pad17)") (class "Default")
      (node (ref "U1") (pin "17") (pinfunction "PA3_17") (pintype "bidirectional"))
    )
    (net (code "64") (name "unconnected-(U1A-PA4-Pad20)") (class "Default")
      (node (ref "U1") (pin "20") (pinfunction "PA4_20") (pintype "bidirectional"))
    )
    (net (code "65") (name "unconnected-(U1A-PA8-Pad41)") (class "Default")
      (node (ref "U1") (pin "41") (pinfunction "PA8_41") (pintype "bidirectional"))
    )
    (net (code "66") (name "unconnected-(U1A-PA11-Pad44)") (class "Default")
      (node (ref "U1") (pin "44") (pinfunction "PA11_44") (pintype "bidirectional"))
    )
    (net (code "67") (name "unconnected-(U1A-PA12-Pad45)") (class "Default")
      (node (ref "U1") (pin "45") (pinfunction "PA12_45") (pintype "bidirectional"))
    )
    (net (code "68") (name "unconnected-(U1A-PB0-Pad26)") (class "Default")
      (node (ref "U1") (pin "26") (pinfunction "PB0_26") (pintype "bidirectional"))
    )
    (net (code "69") (name "unconnected-(U1A-PB1-Pad27)") (class "Default")
      (node (ref "U1") (pin "27") (pinfunction "PB1_27") (pintype "bidirectional"))
    )
    (net (code "70") (name "unconnected-(U1A-PB2-Pad28)") (class "Default")
      (node (ref "U1") (pin "28") (pinfunction "PB2_28") (pintype "bidirectional"))
    )
    (net (code "71") (name "unconnected-(U1A-PB3-Pad55)") (class "Default")
      (node (ref "U1") (pin "55") (pinfunction "PB3_55") (pintype "bidirectional"))
    )
    (net (code "72") (name "unconnected-(U1A-PB4-Pad56)") (class "Default")
      (node (ref "U1") (pin "56") (pinfunction "PB4_56") (pintype "bidirectional"))
    )
    (net (code "73") (name "unconnected-(U1A-PB5-Pad57)") (class "Default")
      (node (ref "U1") (pin "57") (pinfunction "PB5_57") (pintype "bidirectional"))
    )
    (net (code "74") (name "unconnected-(U1A-PB6-Pad58)") (class "Default")
      (node (ref "U1") (pin "58") (pinfunction "PB6_58") (pintype "bidirectional"))
    )
    (net (code "75") (name "unconnected-(U1A-PB7-Pad59)") (class "Default")
      (node (ref "U1") (pin "59") (pinfunction "PB7_59") (pintype "bidirectional"))
    )
    (net (code "76") (name "unconnected-(U1A-PB8-Pad61)") (class "Default")
      (node (ref "U1") (pin "61") (pinfunction "PB8_61") (pintype "bidirectional"))
    )
    (net (code "77") (name "unconnected-(U1A-PB9-Pad62)") (class "Default")
      (node (ref "U1") (pin "62") (pinfunction "PB9_62") (pintype "bidirectional"))
    )
    (net (code "78") (name "unconnected-(U1A-PB12-Pad33)") (class "Default")
      (node (ref "U1") (pin "33") (pinfunction "PB12_33") (pintype "bidirectional"))
    )
    (net (code "79") (name "unconnected-(U1A-PB13-Pad34)") (class "Default")
      (node (ref "U1") (pin "34") (pinfunction "PB13_34") (pintype "bidirectional"))
    )
    (net (code "80") (name "unconnected-(U1A-PB14-Pad35)") (class "Default")
      (node (ref "U1") (pin "35") (pinfunction "PB14_35") (pintype "bidirectional"))
    )
    (net (code "81") (name "unconnected-(U1A-PB15-Pad36)") (class "Default")
      (node (ref "U1") (pin "36") (pinfunction "PB15_36") (pintype "bidirectional"))
    )
    (net (code "82") (name "unconnected-(U1A-PC0-Pad8)") (class "Default")
      (node (ref "U1") (pin "8") (pinfunction "PC0_8") (pintype "bidirectional"))
    )
    (net (code "83") (name "unconnected-(U1A-PC1-Pad9)") (class "Default")
      (node (ref "U1") (pin "9") (pinfunction "PC1_9") (pintype "bidirectional"))
    )
    (net (code "84") (name "unconnected-(U1A-PC2-Pad10)") (class "Default")
      (node (ref "U1") (pin "10") (pinfunction "PC2_10") (pintype "bidirectional"))
    )
    (net (code "85") (name "unconnected-(U1A-PC4-Pad24)") (class "Default")
      (node (ref "U1") (pin "24") (pinfunction "PC4_24") (pintype "bidirectional"))
    )
    (net (code "86") (name "unconnected-(U1A-PC5-Pad25)") (class "Default")
      (node (ref "U1") (pin "25") (pinfunction "PC5_25") (pintype "bidirectional"))
    )
    (net (code "87") (name "unconnected-(U1A-PC6-Pad37)") (class "Default")
      (node (ref "U1") (pin "37") (pinfunction "PC6_37") (pintype "bidirectional"))
    )
    (net (code "88") (name "unconnected-(U1A-PC7-Pad38)") (class "Default")
      (node (ref "U1") (pin "38") (pinfunction "PC7_38") (pintype "bidirectional"))
    )
    (net (code "89") (name "unconnected-(U1A-PC10-Pad51)") (class "Default")
      (node (ref "U1") (pin "51") (pinfunction "PC10_51") (pintype "bidirectional"))
    )
    (net (code "90") (name "unconnected-(U1A-PC11-Pad52)") (class "Default")
      (node (ref "U1") (pin "52") (pinfunction "PC11_52") (pintype "bidirectional"))
    )
    (net (code "91") (name "unconnected-(U1A-PC12-Pad53)") (class "Default")
      (node (ref "U1") (pin "53") (pinfunction "PC12_53") (pintype "bidirectional"))
    )
    (net (code "92") (name "unconnected-(U1A-PC13-TAMPER-RTC-Pad2)") (class "Default")
      (node (ref "U1") (pin "2") (pinfunction "PC13-TAMPER-RTC_2") (pintype "bidirectional"))
    )
    (net (code "93") (name "unconnected-(U1A-PD2-Pad54)") (class "Default")
      (node (ref "U1") (pin "54") (pinfunction "PD2_54") (pintype "bidirectional"))
    )
    (net (code "94") (name "unconnected-(U2-EAR_L-Pad23)") (class "Default")
      (node (ref "U2") (pin "23") (pinfunction "EAR_L_23") (pintype "passive"))
    )
    (net (code "95") (name "unconnected-(U2-EAR_R-Pad24)") (class "Default")
      (node (ref "U2") (pin "24") (pinfunction "EAR_R_24") (pintype "passive"))
    )
    (net (code "96") (name "unconnected-(U2-GPIO1{slash}INT-Pad9)") (class "Default")
      (node (ref "U2") (pin "9") (pinfunction "GPIO1/INT_9") (pintype "passive"))
    )
    (net (code "97") (name "unconnected-(U2-MIC+-Pad20)") (class "Default")
      (node (ref "U2") (pin "20") (pinfunction "MIC+_20") (pintype "passive"))
    )
    (net (code "98") (name "unconnected-(U2-MIC--Pad19)") (class "Default")
      (node (ref "U2") (pin "19") (pinfunction "MIC-_19") (pintype "passive"))
    )
    (net (code "99") (name "unconnected-(U2-MIC2_P-Pad21)") (class "Default")
      (node (ref "U2") (pin "21") (pinfunction "MIC2_P_21") (pintype "passive"))
    )
    (net (code "100") (name "unconnected-(U2-NC-Pad1)") (class "Default")
      (node (ref "U2") (pin "1") (pinfunction "NC_1") (pintype "passive"))
    )
    (net (code "101") (name "unconnected-(U2-NC-Pad2)") (class "Default")
      (node (ref "U2") (pin "2") (pinfunction "NC_2") (pintype "passive"))
    )
    (net (code "102") (name "unconnected-(U2-NC-Pad3)") (class "Default")
      (node (ref "U2") (pin "3") (pinfunction "NC_3") (pintype "passive"))
    )
    (net (code "103") (name "unconnected-(U2-NC-Pad4)") (class "Default")
      (node (ref "U2") (pin "4") (pinfunction "NC_4") (pintype "passive"))
    )
    (net (code "104") (name "unconnected-(U2-NC-Pad5)") (class "Default")
      (node (ref "U2") (pin "5") (pinfunction "NC_5") (pintype "passive"))
    )
    (net (code "105") (name "unconnected-(U2-NC-Pad37)") (class "Default")
      (node (ref "U2") (pin "37") (pinfunction "NC_37") (pintype "passive"))
    )
    (net (code "106") (name "unconnected-(U2-NC-Pad38)") (class "Default")
      (node (ref "U2") (pin "38") (pinfunction "NC_38") (pintype "passive"))
    )
    (net (code "107") (name "unconnected-(U2-REC+-Pad26)") (class "Default")
      (node (ref "U2") (pin "26") (pinfunction "REC+_26") (pintype "passive"))
    )
    (net (code "108") (name "unconnected-(U2-REC--Pad27)") (class "Default")
      (node (ref "U2") (pin "27") (pinfunction "REC-_27") (pintype "passive"))
    )
    (net (code "109") (name "unconnected-(U2-UART_CTS{slash}GPIO5-Pad10)") (class "Default")
      (node (ref "U2") (pin "10") (pinfunction "UART_CTS/GPIO5_10") (pintype "passive"))
    )
    (net (code "110") (name "unconnected-(U2-UART_RTS{slash}GPIO7-Pad11)") (class "Default")
      (node (ref "U2") (pin "11") (pinfunction "UART_RTS/GPIO7_11") (pintype "passive"))
    )
    (net (code "111") (name "unconnected-(U2-VDD_1V8_OUT-Pad29)") (class "Default")
      (node (ref "U2") (pin "29") (pinfunction "VDD_1V8_OUT_29") (pintype "passive"))
    )
  )
)
